# Interactive.net
KiCad netlist of a schematic drawn in Altium Designer
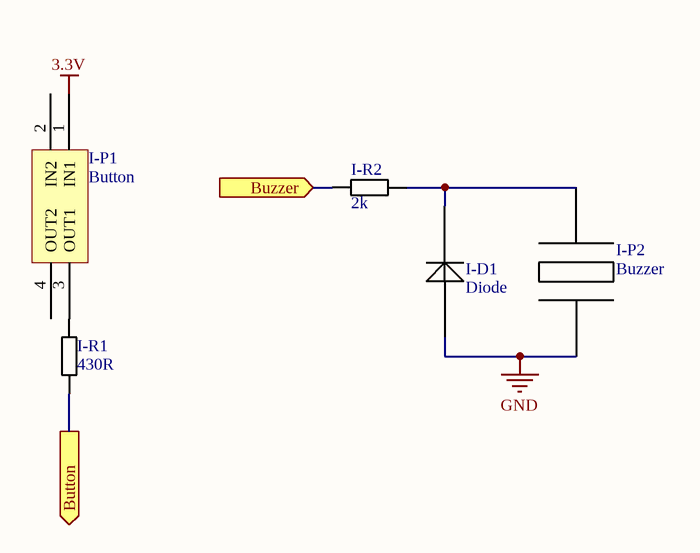
[diagram p0: Interactive.SchDoc]

(export (version "E")
  (design (tool "Eeschema 10.0.6"))
  (components
    (comp (ref "I-D1") (value "Diode") (footprint "SC-90") (libsource (lib "Standard") (part "Diode")))
    (comp (ref "I-P1") (value "Button") (footprint "Button") (libsource (lib "Interactive") (part "Button")))
    (comp (ref "I-P2")
      (value "Buzzer")
      (footprint "PKLCS1212E2000-R1")
      (libsource (lib "Interactive") (part "Buzzer"))
    )
    (comp (ref "I-R1")
      (value "430R")
      (footprint "R 0805 / 2012")
      (libsource (lib "Standard") (part "Resistor"))
    )
    (comp (ref "I-R2") (value "2k") (footprint "R 0805 / 2012") (libsource (lib "") (part "Resistor_1")))
  )
  (nets
    (net (code "1") (name "/Button") (class "Default")
      (node (ref "I-R1") (pin "1") (pinfunction "1_1") (pintype "passive"))
    )
    (net (code "2") (name "/Buzzer") (class "Default")
      (node (ref "I-R2") (pin "2") (pinfunction "2_2") (pintype "passive"))
    )
    (net (code "3") (name "3.3V") (class "Default")
      (node (ref "I-P1") (pin "1") (pinfunction "IN1_1") (pintype "passive"))
    )
    (net (code "4") (name "GND") (class "Default")
      (node (ref "I-D1") (pin "2") (pinfunction "2_2") (pintype "passive"))
      (node (ref "I-P2") (pin "2") (pinfunction "-_2") (pintype "passive"))
    )
    (net (code "5") (name "Net-(I-P1-OUT1)") (class "Default")
      (node (ref "I-P1") (pin "3") (pinfunction "OUT1_3") (pintype "passive"))
      (node (ref "I-R1") (pin "2") (pinfunction "2_2") (pintype "passive"))
    )
    (net (code "6") (name "Net-(I-P2-+)") (class "Default")
      (node (ref "I-D1") (pin "1") (pinfunction "1_1") (pintype "passive"))
      (node (ref "I-P2") (pin "1") (pinfunction "+_1") (pintype "passive"))
      (node (ref "I-R2") (pin "1") (pinfunction "1_1") (pintype "passive"))
    )
    (net (code "7") (name "unconnected-(I-P1-IN2-Pad2)") (class "Default")
      (node (ref "I-P1") (pin "2") (pinfunction "IN2_2") (pintype "passive"))
    )
    (net (code "8") (name "unconnected-(I-P1-OUT2-Pad4)") (class "Default")
      (node (ref "I-P1") (pin "4") (pinfunction "OUT2_4") (pintype "passive"))
    )
  )
)
